# Sheet1.net
KiCad netlist of a schematic drawn in Altium Designer
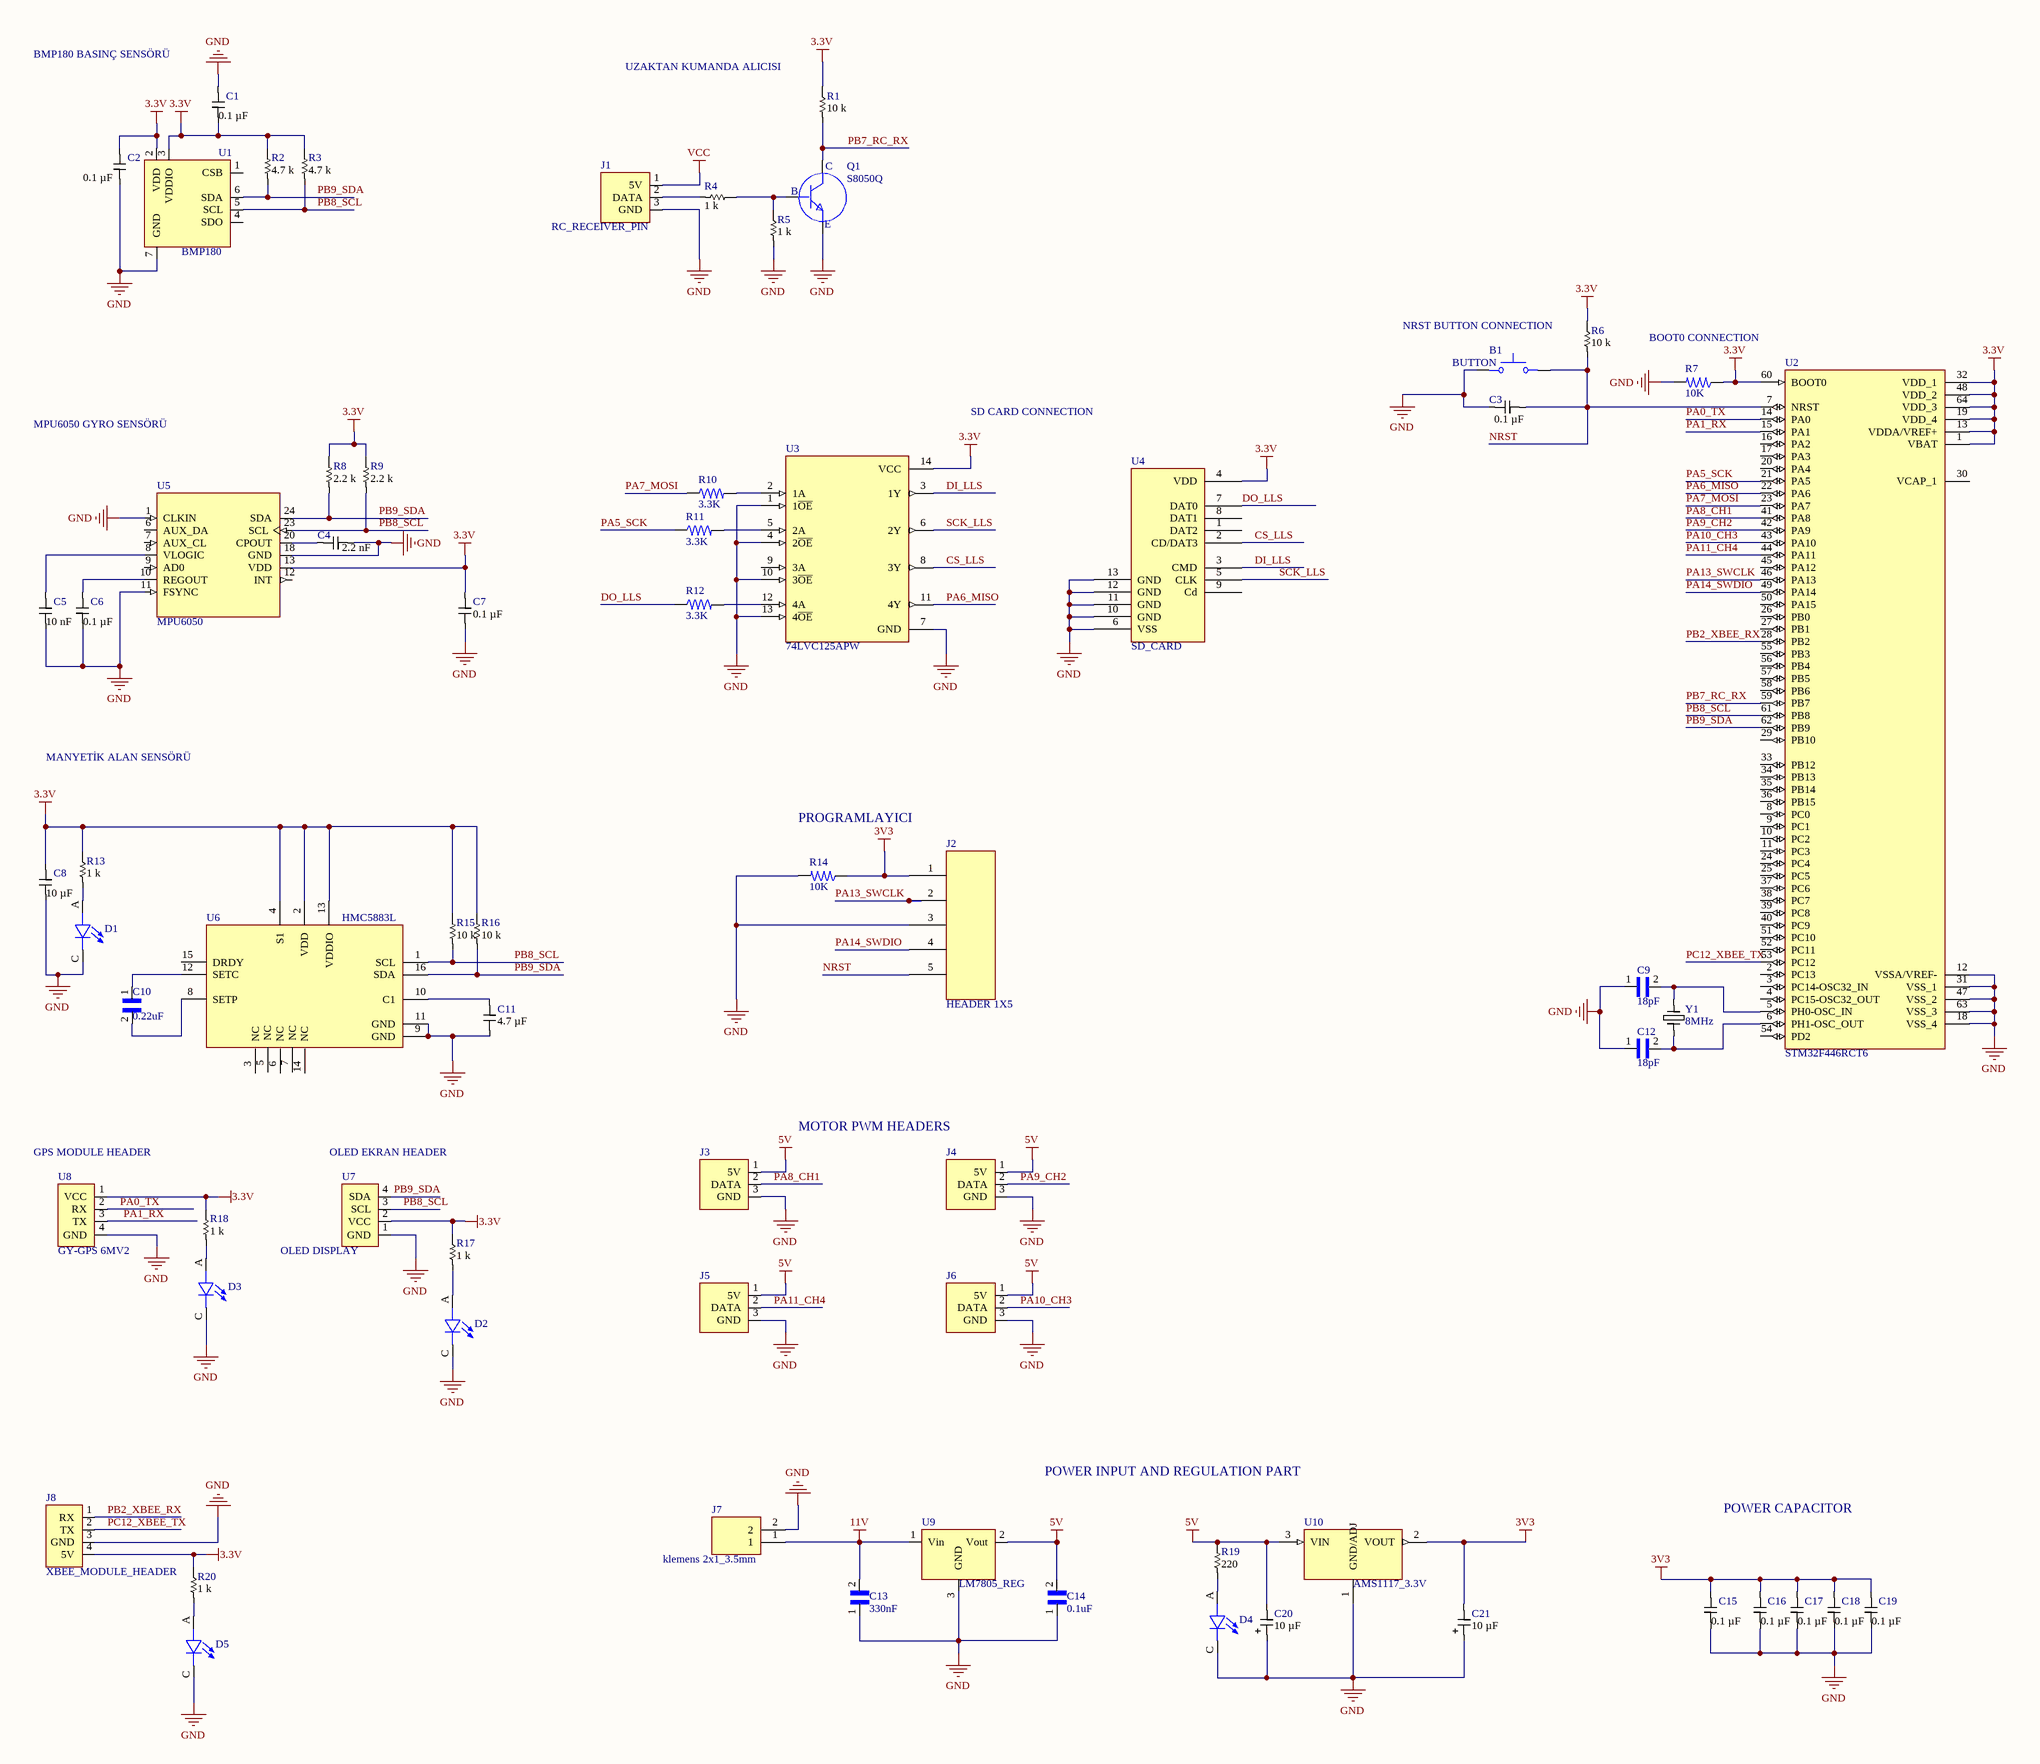
[diagram p0: Sheet1.SchDoc]

(export (version "E")
  (design (tool "Eeschema 10.0.6"))
  (components
    (comp (ref "B1") (value "BUTTON") (footprint "BUTTON") (libsource (lib "Schlib1") (part "BUTTON")))
    (comp (ref "C1")
      (value "CL10B104KB8NNNC")
      (footprint "SAMSUNG_CAP_0603_090")
      (description "CAP CER 0.1UF 50V X7R 0603")
      (fields (field (name "CAPACITANCE") "0.1 µF"))
      (libsource (lib "Ceramic Capacitors") (part "CL10B104KB8NNNC"))
    )
    (comp (ref "C2")
      (value "CL10B104KB8NNNC")
      (footprint "SAMSUNG_CAP_0603_090")
      (description "CAP CER 0.1UF 50V X7R 0603")
      (fields (field (name "CAPACITANCE") "0.1 µF"))
      (libsource (lib "Ceramic Capacitors") (part "CL10B104KB8NNNC"))
    )
    (comp (ref "C3")
      (value "CL10B104KB8NNNC")
      (footprint "SAMSUNG_CAP_0603_090")
      (description "CAP CER 0.1UF 50V X7R 0603")
      (fields (field (name "CAPACITANCE") "0.1 µF"))
      (libsource (lib "Ceramic Capacitors") (part "CL10B104KB8NNNC"))
    )
    (comp (ref "C4")
      (value "CL10B222KB8NNNC")
      (footprint "SAMSUNG_CAP_0603_090")
      (description "CAP CER 2200PF 50V X7R 0603")
      (fields (field (name "CAPACITANCE") "2.2 nF"))
      (libsource (lib "Ceramic Capacitors") (part "CL10B222KB8NNNC"))
    )
    (comp (ref "C5")
      (value "CL10B103KB8NNNL")
      (footprint "SAMSUNG_CAP_0603_090")
      (description "CAP CER 10000PF 50V X7R 0603")
      (fields (field (name "CAPACITANCE") "10 nF"))
      (libsource (lib "Ceramic Capacitors") (part "CL10B103KB8NNNL"))
    )
    (comp (ref "C6")
      (value "CL10B104KB8NNNC")
      (footprint "SAMSUNG_CAP_0603_090")
      (description "CAP CER 0.1UF 50V X7R 0603")
      (fields (field (name "CAPACITANCE") "0.1 µF"))
      (libsource (lib "Ceramic Capacitors") (part "CL10B104KB8NNNC"))
    )
    (comp (ref "C7")
      (value "CL10B104KB8NNNC")
      (footprint "SAMSUNG_CAP_0603_090")
      (description "CAP CER 0.1UF 50V X7R 0603")
      (fields (field (name "CAPACITANCE") "0.1 µF"))
      (libsource (lib "Ceramic Capacitors") (part "CL10B104KB8NNNC"))
    )
    (comp (ref "C8")
      (value "CL21B106KPQNNNE")
      (footprint "SAMSUNG_CAP_0805_140")
      (description "CAP CER 10UF 10V X7R 0805")
      (fields (field (name "CAPACITANCE") "10 µF"))
      (libsource (lib "Ceramic Capacitors") (part "CL21B106KPQNNNE"))
    )
    (comp (ref "C9")
      (value "18pF")
      (footprint "18pF capacitor")
      (libsource (lib "Schlib1") (part "capacitor 18pF"))
    )
    (comp (ref "C10")
      (value "0.22uF")
      (footprint "0.22uF CAPACITOR")
      (libsource (lib "Schlib1") (part "0.22uF CAPACITOR"))
    )
    (comp (ref "C11")
      (value "CL21A475KACLRNC")
      (footprint "SAMSUNG_CAP_0805_095")
      (description "CAP CER 4.7UF 25V X5R 0805")
      (fields (field (name "CAPACITANCE") "4.7 µF"))
      (libsource (lib "Ceramic Capacitors") (part "CL21A475KACLRNC"))
    )
    (comp (ref "C12")
      (value "18pF")
      (footprint "18pF capacitor")
      (libsource (lib "Schlib1") (part "capacitor 18pF"))
    )
    (comp (ref "C13")
      (value "330nF")
      (footprint "1206CAPACITOR")
      (libsource (lib "Sch1-schlib") (part "1206CAPACITOR"))
    )
    (comp (ref "C14")
      (value "0.1uF")
      (footprint "1206CAPACITOR")
      (libsource (lib "Sch1-schlib") (part "1206CAPACITOR"))
    )
    (comp (ref "C15")
      (value "CL10B104KB8NNNC")
      (footprint "SAMSUNG_CAP_0603_090")
      (description "CAP CER 0.1UF 50V X7R 0603")
      (fields (field (name "CAPACITANCE") "0.1 µF"))
      (libsource (lib "Ceramic Capacitors") (part "CL10B104KB8NNNC"))
    )
    (comp (ref "C16")
      (value "CL10B104KB8NNNC")
      (footprint "SAMSUNG_CAP_0603_090")
      (description "CAP CER 0.1UF 50V X7R 0603")
      (fields (field (name "CAPACITANCE") "0.1 µF"))
      (libsource (lib "Ceramic Capacitors") (part "CL10B104KB8NNNC"))
    )
    (comp (ref "C17")
      (value "CL10B104KB8NNNC")
      (footprint "SAMSUNG_CAP_0603_090")
      (description "CAP CER 0.1UF 50V X7R 0603")
      (fields (field (name "CAPACITANCE") "0.1 µF"))
      (libsource (lib "Ceramic Capacitors") (part "CL10B104KB8NNNC"))
    )
    (comp (ref "C18")
      (value "CL10B104KB8NNNC")
      (footprint "SAMSUNG_CAP_0603_090")
      (description "CAP CER 0.1UF 50V X7R 0603")
      (fields (field (name "CAPACITANCE") "0.1 µF"))
      (libsource (lib "Ceramic Capacitors") (part "CL10B104KB8NNNC"))
    )
    (comp (ref "C19")
      (value "CL10B104KB8NNNC")
      (footprint "SAMSUNG_CAP_0603_090")
      (description "CAP CER 0.1UF 50V X7R 0603")
      (fields (field (name "CAPACITANCE") "0.1 µF"))
      (libsource (lib "Ceramic Capacitors") (part "CL10B104KB8NNNC"))
    )
    (comp (ref "C20")
      (value "T491B106M016AT")
      (footprint "KEMET_CAP_TAN-B")
      (description "CAP TANT 10UF 20% 16V 1411")
      (fields (field (name "CAPACITANCE") "10 µF"))
      (libsource (lib "Tantalum Capacitors") (part "T491B106M016AT"))
    )
    (comp (ref "C21")
      (value "T491B106M016AT")
      (footprint "KEMET_CAP_TAN-B")
      (description "CAP TANT 10UF 20% 16V 1411")
      (fields (field (name "CAPACITANCE") "10 µF"))
      (libsource (lib "Tantalum Capacitors") (part "T491B106M016AT"))
    )
    (comp (ref "D1")
      (value "MP-2016-1100-30-80")
      (footprint "LED_MP-2016-1100-30-80")
      (description "LED Midpower Lighting series White, warm 3000K, 80 CRI, 27lm 3V 120mA 110Â°")
      (fields (field (name "MF") "Luminus Devices"))
      (libsource (lib "MP-2016-1100-30-80") (part "MP-2016-1100-30-80"))
    )
    (comp (ref "D2")
      (value "MP-2016-1100-30-80")
      (footprint "LED_MP-2016-1100-30-80")
      (description "LED Midpower Lighting series White, warm 3000K, 80 CRI, 27lm 3V 120mA 110Â°")
      (fields (field (name "MF") "Luminus Devices"))
      (libsource (lib "MP-2016-1100-30-80") (part "MP-2016-1100-30-80"))
    )
    (comp (ref "D3")
      (value "MP-2016-1100-30-80")
      (footprint "LED_MP-2016-1100-30-80")
      (description "LED Midpower Lighting series White, warm 3000K, 80 CRI, 27lm 3V 120mA 110Â°")
      (fields (field (name "MF") "Luminus Devices"))
      (libsource (lib "MP-2016-1100-30-80") (part "MP-2016-1100-30-80"))
    )
    (comp (ref "D4")
      (value "MP-2016-1100-30-80")
      (footprint "LED_MP-2016-1100-30-80")
      (description "LED Midpower Lighting series White, warm 3000K, 80 CRI, 27lm 3V 120mA 110Â°")
      (fields (field (name "MF") "Luminus Devices"))
      (libsource (lib "MP-2016-1100-30-80") (part "MP-2016-1100-30-80"))
    )
    (comp (ref "D5")
      (value "MP-2016-1100-30-80")
      (footprint "LED_MP-2016-1100-30-80")
      (description "LED Midpower Lighting series White, warm 3000K, 80 CRI, 27lm 3V 120mA 110Â°")
      (fields (field (name "MF") "Luminus Devices"))
      (libsource (lib "MP-2016-1100-30-80") (part "MP-2016-1100-30-80"))
    )
    (comp (ref "J1")
      (value "RC_RECEIVER_PIN")
      (footprint "RC_RECEIVER_PIN")
      (libsource (lib "Schlib1") (part "RC_RECEIVER_PIN"))
    )
    (comp (ref "J2")
      (value "HEADER 1X5")
      (footprint "HEADER 1X5_2.54mm")
      (libsource (lib "Sch1-schlib") (part "HEADER 1X5"))
    )
    (comp (ref "J3")
      (value "MOTOR_PWM_HEADER")
      (footprint "MOTOR_PWM_HEADER")
      (libsource (lib "Schlib1") (part "MOTOR_PWM_HEADER"))
    )
    (comp (ref "J4")
      (value "MOTOR_PWM_HEADER")
      (footprint "MOTOR_PWM_HEADER")
      (libsource (lib "Schlib1") (part "MOTOR_PWM_HEADER"))
    )
    (comp (ref "J5")
      (value "MOTOR_PWM_HEADER")
      (footprint "MOTOR_PWM_HEADER")
      (libsource (lib "Schlib1") (part "MOTOR_PWM_HEADER"))
    )
    (comp (ref "J6")
      (value "MOTOR_PWM_HEADER")
      (footprint "MOTOR_PWM_HEADER")
      (libsource (lib "Schlib1") (part "MOTOR_PWM_HEADER"))
    )
    (comp (ref "J7")
      (value "klemens 2x1_3.5mm")
      (footprint "KLEMENS 2X1_3.5mm - duplicate")
      (libsource (lib "Sch1-schlib") (part "klemens 2x1_3.5mm"))
    )
    (comp (ref "J8")
      (value "XBEE_MODULE_HEADER")
      (footprint "XBEE_MODULE_HEADER")
      (libsource (lib "Schlib1") (part "XBEE_MODULE_HEADER"))
    )
    (comp (ref "Q1")
      (value "S8050Q")
      (footprint "S8050Q")
      (description "BJT TRANSİSTOR 25V 0.5mA")
      (libsource (lib "Schlib1") (part "S8050Q"))
    )
    (comp (ref "R1")
      (value "0603SAJ0103T5E")
      (footprint "ROYALOHM_RES_0603")
      (description "RES SMD 10K OHM 5% 1/10W 0603")
      (fields (field (name "RESISTANCE") "10 k"))
      (libsource (lib "Chip Resistor - Surface Mount") (part "0603SAJ0103T5E"))
    )
    (comp (ref "R2")
      (value "0603SAJ0472TDE")
      (footprint "ROYALOHM_RES_0603")
      (description "RES SMD 4.7K OHM 5% 1/10W 0603")
      (fields (field (name "RESISTANCE") "4.7 k"))
      (libsource (lib "Chip Resistor - Surface Mount") (part "0603SAJ0472TDE"))
    )
    (comp (ref "R3")
      (value "0603SAJ0472TDE")
      (footprint "ROYALOHM_RES_0603")
      (description "RES SMD 4.7K OHM 5% 1/10W 0603")
      (fields (field (name "RESISTANCE") "4.7 k"))
      (libsource (lib "Chip Resistor - Surface Mount") (part "0603SAJ0472TDE"))
    )
    (comp (ref "R4")
      (value "0603SAJ0102T5E")
      (footprint "ROYALOHM_RES_0603")
      (description "RES SMD 1K OHM 5% 1/10W 0603")
      (fields (field (name "RESISTANCE") "1 k"))
      (libsource (lib "Chip Resistor - Surface Mount") (part "0603SAJ0102T5E"))
    )
    (comp (ref "R5")
      (value "0603SAJ0102T5E")
      (footprint "ROYALOHM_RES_0603")
      (description "RES SMD 1K OHM 5% 1/10W 0603")
      (fields (field (name "RESISTANCE") "1 k"))
      (libsource (lib "Chip Resistor - Surface Mount") (part "0603SAJ0102T5E"))
    )
    (comp (ref "R6")
      (value "0603SAJ0103T5E")
      (footprint "ROYALOHM_RES_0603")
      (description "RES SMD 10K OHM 5% 1/10W 0603")
      (fields (field (name "RESISTANCE") "10 k"))
      (libsource (lib "Chip Resistor - Surface Mount") (part "0603SAJ0103T5E"))
    )
    (comp (ref "R7") (value "10K") (footprint "RES") (libsource (lib "Sch1-schlib") (part "RES")))
    (comp (ref "R8")
      (value "0805S8J0222T5E")
      (footprint "ROYALOHM_RES_0805")
      (description "RES SMD 2.2K OHM 5% 1/8W 0805")
      (fields (field (name "RESISTANCE") "2.2 k"))
      (libsource (lib "Chip Resistor - Surface Mount") (part "0805S8J0222T5E"))
    )
    (comp (ref "R9")
      (value "0805S8J0222T5E")
      (footprint "ROYALOHM_RES_0805")
      (description "RES SMD 2.2K OHM 5% 1/8W 0805")
      (fields (field (name "RESISTANCE") "2.2 k"))
      (libsource (lib "Chip Resistor - Surface Mount") (part "0805S8J0222T5E"))
    )
    (comp (ref "R10")
      (value "3.3K")
      (footprint "0805 cap RES")
      (description "RES 0.33 OHM 1% 1/4W 0805              0805 cap RES")
      (libsource (lib "Schlib1") (part "0805 cap RES"))
    )
    (comp (ref "R11")
      (value "3.3K")
      (footprint "0805 cap RES")
      (description "RES 0.33 OHM 1% 1/4W 0805              0805 cap RES")
      (libsource (lib "Schlib1") (part "0805 cap RES"))
    )
    (comp (ref "R12")
      (value "3.3K")
      (footprint "0805 cap RES")
      (description "RES 0.33 OHM 1% 1/4W 0805              0805 cap RES")
      (libsource (lib "Schlib1") (part "0805 cap RES"))
    )
    (comp (ref "R13")
      (value "0603SAJ0102T5E")
      (footprint "ROYALOHM_RES_0603")
      (description "RES SMD 1K OHM 5% 1/10W 0603")
      (fields (field (name "RESISTANCE") "1 k"))
      (libsource (lib "Chip Resistor - Surface Mount") (part "0603SAJ0102T5E"))
    )
    (comp (ref "R14") (value "10K") (footprint "RES") (libsource (lib "Sch1-schlib") (part "RES")))
    (comp (ref "R15")
      (value "0603SAJ0103T5E")
      (footprint "ROYALOHM_RES_0603")
      (description "RES SMD 10K OHM 5% 1/10W 0603")
      (fields (field (name "RESISTANCE") "10 k"))
      (libsource (lib "Chip Resistor - Surface Mount") (part "0603SAJ0103T5E"))
    )
    (comp (ref "R16")
      (value "0603SAJ0103T5E")
      (footprint "ROYALOHM_RES_0603")
      (description "RES SMD 10K OHM 5% 1/10W 0603")
      (fields (field (name "RESISTANCE") "10 k"))
      (libsource (lib "Chip Resistor - Surface Mount") (part "0603SAJ0103T5E"))
    )
    (comp (ref "R17")
      (value "0603SAJ0102T5E")
      (footprint "ROYALOHM_RES_0603")
      (description "RES SMD 1K OHM 5% 1/10W 0603")
      (fields (field (name "RESISTANCE") "1 k"))
      (libsource (lib "Chip Resistor - Surface Mount") (part "0603SAJ0102T5E"))
    )
    (comp (ref "R18")
      (value "0603SAJ0102T5E")
      (footprint "ROYALOHM_RES_0603")
      (description "RES SMD 1K OHM 5% 1/10W 0603")
      (fields (field (name "RESISTANCE") "1 k"))
      (libsource (lib "Chip Resistor - Surface Mount") (part "0603SAJ0102T5E"))
    )
    (comp (ref "R19")
      (value "0603SAJ0221T5E")
      (footprint "ROYALOHM_RES_0603")
      (description "RES SMD 220R OHM 5% 1/10W 0603")
      (fields (field (name "RESISTANCE") "220"))
      (libsource (lib "Chip Resistor - Surface Mount") (part "0603SAJ0221T5E"))
    )
    (comp (ref "R20")
      (value "0603SAJ0102T5E")
      (footprint "ROYALOHM_RES_0603")
      (description "RES SMD 1K OHM 5% 1/10W 0603")
      (fields (field (name "RESISTANCE") "1 k"))
      (libsource (lib "Chip Resistor - Surface Mount") (part "0603SAJ0102T5E"))
    )
    (comp (ref "U1")
      (value "BMP180")
      (footprint "BMP180")
      (description "PRESSURE SENSOR")
      (libsource (lib "Schlib1") (part "BMP180"))
    )
    (comp (ref "U2")
      (value "STM32F446RCT6")
      (footprint "STM32F446RCT6")
      (libsource (lib "Schlib1") (part "STM32F446RCT6"))
    )
    (comp (ref "U3")
      (value "74LVC125APW")
      (footprint "74LVC125APW")
      (libsource (lib "Schlib1") (part "74LVC125APW"))
    )
    (comp (ref "U4") (value "SD_CARD") (footprint "SD_CARD") (libsource (lib "Schlib1") (part "SD_CARD")))
    (comp (ref "U5") (value "MPU6050") (footprint "MPU6050") (libsource (lib "Schlib1") (part "MPU6050")))
    (comp (ref "U6") (value "HMC5883L") (footprint "HMC5883L") (libsource (lib "Schlib1") (part "HMC5883L")))
    (comp (ref "U7")
      (value "OLED DISPLAY")
      (footprint "OLED DISPLAY")
      (libsource (lib "Schlib1") (part "OLED DISPLAY"))
    )
    (comp (ref "U8")
      (value "GY-GPS 6MV2")
      (footprint "GY-GPS 6MV2")
      (libsource (lib "Schlib1") (part "GY-GPS 6MV2"))
    )
    (comp (ref "U9")
      (value "LM7805_REG")
      (footprint "DPAK228P968X230-3N")
      (libsource (lib "Schlib1") (part "LM7805_REG"))
    )
    (comp (ref "U10")
      (value "AMS1117_3.3V")
      (footprint "AMS1117_3.3V")
      (libsource (lib "Schlib1") (part "AMS1117_3.3V"))
    )
    (comp (ref "Y1")
      (value "8MHz")
      (footprint "ABM3-8.000MHZ-D2Y-T")
      (libsource (lib "Schlib1") (part "ABM3-8.000MHZ-D2Y-T"))
    )
  )
  (nets
    (net (code "1") (name "/CS_LLS") (class "Default")
      (node (ref "U3") (pin "8") (pinfunction "3Y_8") (pintype "output"))
      (node (ref "U4") (pin "2") (pinfunction "CD/DAT3_2") (pintype "passive"))
    )
    (net (code "2") (name "/DI_LLS") (class "Default")
      (node (ref "U3") (pin "3") (pinfunction "1Y_3") (pintype "output"))
      (node (ref "U4") (pin "3") (pinfunction "CMD_3") (pintype "passive"))
    )
    (net (code "3") (name "/DO_LLS") (class "Default")
      (node (ref "R12") (pin "1") (pinfunction "1_1") (pintype "passive"))
      (node (ref "U4") (pin "7") (pinfunction "DAT0_7") (pintype "passive"))
    )
    (net (code "4") (name "/NRST") (class "Default")
      (node (ref "B1") (pin "3") (pinfunction "3_3") (pintype "passive"))
      (node (ref "C3") (pin "2") (pinfunction "2_2") (pintype "passive"))
      (node (ref "J2") (pin "5") (pintype "passive"))
      (node (ref "R6") (pin "1") (pinfunction "1_1") (pintype "passive"))
      (node (ref "U2") (pin "7") (pinfunction "NRST_7") (pintype "bidirectional"))
    )
    (net (code "5") (name "/PA0_TX") (class "Default")
      (node (ref "U2") (pin "14") (pinfunction "PA0_14") (pintype "bidirectional"))
      (node (ref "U8") (pin "2") (pinfunction "RX_2") (pintype "passive"))
    )
    (net (code "6") (name "/PA1_RX") (class "Default")
      (node (ref "U2") (pin "15") (pinfunction "PA1_15") (pintype "bidirectional"))
      (node (ref "U8") (pin "3") (pinfunction "TX_3") (pintype "passive"))
    )
    (net (code "7") (name "/PA5_SCK") (class "Default")
      (node (ref "R11") (pin "1") (pinfunction "1_1") (pintype "passive"))
      (node (ref "U2") (pin "21") (pinfunction "PA5_21") (pintype "bidirectional"))
    )
    (net (code "8") (name "/PA6_MISO") (class "Default")
      (node (ref "U2") (pin "22") (pinfunction "PA6_22") (pintype "bidirectional"))
      (node (ref "U3") (pin "11") (pinfunction "4Y_11") (pintype "output"))
    )
    (net (code "9") (name "/PA7_MOSI") (class "Default")
      (node (ref "R10") (pin "1") (pinfunction "1_1") (pintype "passive"))
      (node (ref "U2") (pin "23") (pinfunction "PA7_23") (pintype "bidirectional"))
    )
    (net (code "10") (name "/PA8_CH1") (class "Default")
      (node (ref "J3") (pin "2") (pinfunction "DATA_2") (pintype "passive"))
      (node (ref "U2") (pin "41") (pinfunction "PA8_41") (pintype "bidirectional"))
    )
    (net (code "11") (name "/PA9_CH2") (class "Default")
      (node (ref "J4") (pin "2") (pinfunction "DATA_2") (pintype "passive"))
      (node (ref "U2") (pin "42") (pinfunction "PA9_42") (pintype "bidirectional"))
    )
    (net (code "12") (name "/PA10_CH3") (class "Default")
      (node (ref "J6") (pin "2") (pinfunction "DATA_2") (pintype "passive"))
      (node (ref "U2") (pin "43") (pinfunction "PA10_43") (pintype "bidirectional"))
    )
    (net (code "13") (name "/PA11_CH4") (class "Default")
      (node (ref "J5") (pin "2") (pinfunction "DATA_2") (pintype "passive"))
      (node (ref "U2") (pin "44") (pinfunction "PA11_44") (pintype "bidirectional"))
    )
    (net (code "14") (name "/PA13_SWCLK") (class "Default")
      (node (ref "J2") (pin "2") (pintype "passive"))
      (node (ref "U2") (pin "46") (pinfunction "PA13_46") (pintype "bidirectional"))
    )
    (net (code "15") (name "/PA14_SWDIO") (class "Default")
      (node (ref "J2") (pin "4") (pintype "passive"))
      (node (ref "U2") (pin "49") (pinfunction "PA14_49") (pintype "bidirectional"))
    )
    (net (code "16") (name "/PB2_XBEE_RX") (class "Default")
      (node (ref "J8") (pin "1") (pinfunction "RX_1") (pintype "passive"))
      (node (ref "U2") (pin "28") (pinfunction "PB2_28") (pintype "bidirectional"))
    )
    (net (code "17") (name "/PB7_RC_RX") (class "Default")
      (node (ref "Q1") (pin "3") (pinfunction "C_3") (pintype "passive"))
      (node (ref "R1") (pin "1") (pinfunction "1_1") (pintype "passive"))
      (node (ref "U2") (pin "59") (pinfunction "PB7_59") (pintype "bidirectional"))
    )
    (net (code "18") (name "/PB8_SCL") (class "Default")
      (node (ref "R15") (pin "1") (pinfunction "1_1") (pintype "passive"))
      (node (ref "R3") (pin "1") (pinfunction "1_1") (pintype "passive"))
      (node (ref "R9") (pin "1") (pinfunction "1_1") (pintype "passive"))
      (node (ref "U1") (pin "5") (pinfunction "SCL_5") (pintype "passive"))
      (node (ref "U2") (pin "61") (pinfunction "PB8_61") (pintype "bidirectional"))
      (node (ref "U5") (pin "23") (pinfunction "SCL_23") (pintype "input"))
      (node (ref "U6") (pin "1") (pinfunction "SCL_1") (pintype "passive"))
      (node (ref "U7") (pin "3") (pinfunction "SCL_3") (pintype "passive"))
    )
    (net (code "19") (name "/PB9_SDA") (class "Default")
      (node (ref "R16") (pin "1") (pinfunction "1_1") (pintype "passive"))
      (node (ref "R2") (pin "1") (pinfunction "1_1") (pintype "passive"))
      (node (ref "R8") (pin "1") (pinfunction "1_1") (pintype "passive"))
      (node (ref "U1") (pin "6") (pinfunction "SDA_6") (pintype "passive"))
      (node (ref "U2") (pin "62") (pinfunction "PB9_62") (pintype "bidirectional"))
      (node (ref "U5") (pin "24") (pinfunction "SDA_24") (pintype "bidirectional"))
      (node (ref "U6") (pin "16") (pinfunction "SDA_16") (pintype "passive"))
      (node (ref "U7") (pin "4") (pinfunction "SDA_4") (pintype "passive"))
    )
    (net (code "20") (name "/PC12_XBEE_TX") (class "Default")
      (node (ref "J8") (pin "2") (pinfunction "TX_2") (pintype "passive"))
      (node (ref "U2") (pin "53") (pinfunction "PC12_53") (pintype "bidirectional"))
    )
    (net (code "21") (name "/SCK_LLS") (class "Default")
      (node (ref "U3") (pin "6") (pinfunction "2Y_6") (pintype "output"))
      (node (ref "U4") (pin "5") (pinfunction "CLK_5") (pintype "passive"))
    )
    (net (code "22") (name "3.3V") (class "Default")
      (node (ref "C1") (pin "2") (pinfunction "2_2") (pintype "passive"))
      (node (ref "C2") (pin "1") (pinfunction "1_1") (pintype "passive"))
      (node (ref "C7") (pin "2") (pinfunction "2_2") (pintype "passive"))
      (node (ref "C8") (pin "2") (pinfunction "2_2") (pintype "passive"))
      (node (ref "J8") (pin "4") (pinfunction "5V_4") (pintype "passive"))
      (node (ref "R1") (pin "2") (pinfunction "2_2") (pintype "passive"))
      (node (ref "R13") (pin "2") (pinfunction "2_2") (pintype "passive"))
      (node (ref "R15") (pin "2") (pinfunction "2_2") (pintype "passive"))
      (node (ref "R16") (pin "2") (pinfunction "2_2") (pintype "passive"))
      (node (ref "R17") (pin "2") (pinfunction "2_2") (pintype "passive"))
      (node (ref "R18") (pin "2") (pinfunction "2_2") (pintype "passive"))
      (node (ref "R2") (pin "2") (pinfunction "2_2") (pintype "passive"))
      (node (ref "R20") (pin "2") (pinfunction "2_2") (pintype "passive"))
      (node (ref "R3") (pin "2") (pinfunction "2_2") (pintype "passive"))
      (node (ref "R6") (pin "2") (pinfunction "2_2") (pintype "passive"))
      (node (ref "R7") (pin "1") (pinfunction "1_1") (pintype "passive"))
      (node (ref "R8") (pin "2") (pinfunction "2_2") (pintype "passive"))
      (node (ref "R9") (pin "2") (pinfunction "2_2") (pintype "passive"))
      (node (ref "U1") (pin "2") (pinfunction "VDD_2") (pintype "passive"))
      (node (ref "U1") (pin "3") (pinfunction "VDDIO_3") (pintype "passive"))
      (node (ref "U2") (pin "1") (pinfunction "VBAT_1") (pintype "power_in"))
      (node (ref "U2") (pin "13") (pinfunction "VDDA/VREF+_13") (pintype "power_in"))
      (node (ref "U2") (pin "19") (pinfunction "VDD_4_19") (pintype "power_in"))
      (node (ref "U2") (pin "32") (pinfunction "VDD_1_32") (pintype "power_in"))
      (node (ref "U2") (pin "48") (pinfunction "VDD_2_48") (pintype "power_in"))
      (node (ref "U2") (pin "60") (pinfunction "BOOT0_60") (pintype "input"))
      (node (ref "U2") (pin "64") (pinfunction "VDD_3_64") (pintype "power_in"))
      (node (ref "U3") (pin "14") (pinfunction "VCC_14") (pintype "power_in"))
      (node (ref "U4") (pin "4") (pinfunction "VDD_4") (pintype "passive"))
      (node (ref "U5") (pin "13") (pinfunction "VDD_13") (pintype "power_in"))
      (node (ref "U6") (pin "13") (pinfunction "VDDIO_13") (pintype "passive"))
      (node (ref "U6") (pin "2") (pinfunction "VDD_2") (pintype "passive"))
      (node (ref "U6") (pin "4") (pinfunction "S1_4") (pintype "passive"))
      (node (ref "U7") (pin "2") (pinfunction "VCC_2") (pintype "passive"))
      (node (ref "U8") (pin "1") (pinfunction "VCC_1") (pintype "passive"))
    )
    (net (code "23") (name "3V3") (class "Default")
      (node (ref "C15") (pin "1") (pinfunction "1_1") (pintype "passive"))
      (node (ref "C16") (pin "1") (pinfunction "1_1") (pintype "passive"))
      (node (ref "C17") (pin "1") (pinfunction "1_1") (pintype "passive"))
      (node (ref "C18") (pin "1") (pinfunction "1_1") (pintype "passive"))
      (node (ref "C19") (pin "1") (pinfunction "1_1") (pintype "passive"))
      (node (ref "C21") (pin "2") (pinfunction "2_2") (pintype "passive"))
      (node (ref "J2") (pin "1") (pintype "passive"))
      (node (ref "R14") (pin "1") (pinfunction "1_1") (pintype "passive"))
      (node (ref "U10") (pin "2") (pinfunction "VOUT_2") (pintype "output"))
    )
    (net (code "24") (name "5V") (class "Default")
      (node (ref "C14") (pin "2") (pinfunction "2_2") (pintype "passive"))
      (node (ref "C20") (pin "2") (pinfunction "2_2") (pintype "passive"))
      (node (ref "J3") (pin "1") (pinfunction "5V_1") (pintype "passive"))
      (node (ref "J4") (pin "1") (pinfunction "5V_1") (pintype "passive"))
      (node (ref "J5") (pin "1") (pinfunction "5V_1") (pintype "passive"))
      (node (ref "J6") (pin "1") (pinfunction "5V_1") (pintype "passive"))
      (node (ref "R19") (pin "2") (pinfunction "2_2") (pintype "passive"))
      (node (ref "U10") (pin "3") (pinfunction "VIN_3") (pintype "input"))
      (node (ref "U9") (pin "2") (pinfunction "Vout_2") (pintype "passive"))
    )
    (net (code "25") (name "11V") (class "Default")
      (node (ref "C13") (pin "2") (pinfunction "2_2") (pintype "passive"))
      (node (ref "J7") (pin "1") (pinfunction "1_1") (pintype "passive"))
      (node (ref "U9") (pin "1") (pinfunction "Vin_1") (pintype "passive"))
    )
    (net (code "26") (name "GND") (class "Default")
      (node (ref "B1") (pin "1") (pinfunction "1_1") (pintype "passive"))
      (node (ref "C1") (pin "1") (pinfunction "1_1") (pintype "passive"))
      (node (ref "C11") (pin "1") (pinfunction "1_1") (pintype "passive"))
      (node (ref "C12") (pin "1") (pinfunction "1_1") (pintype "passive"))
      (node (ref "C13") (pin "1") (pinfunction "1_1") (pintype "passive"))
      (node (ref "C14") (pin "1") (pinfunction "1_1") (pintype "passive"))
      (node (ref "C15") (pin "2") (pinfunction "2_2") (pintype "passive"))
      (node (ref "C16") (pin "2") (pinfunction "2_2") (pintype "passive"))
      (node (ref "C17") (pin "2") (pinfunction "2_2") (pintype "passive"))
      (node (ref "C18") (pin "2") (pinfunction "2_2") (pintype "passive"))
      (node (ref "C19") (pin "2") (pinfunction "2_2") (pintype "passive"))
      (node (ref "C2") (pin "2") (pinfunction "2_2") (pintype "passive"))
      (node (ref "C20") (pin "1") (pinfunction "1_1") (pintype "passive"))
      (node (ref "C21") (pin "1") (pinfunction "1_1") (pintype "passive"))
      (node (ref "C3") (pin "1") (pinfunction "1_1") (pintype "passive"))
      (node (ref "C4") (pin "2") (pinfunction "2_2") (pintype "passive"))
      (node (ref "C5") (pin "1") (pinfunction "1_1") (pintype "passive"))
      (node (ref "C6") (pin "2") (pinfunction "2_2") (pintype "passive"))
      (node (ref "C7") (pin "1") (pinfunction "1_1") (pintype "passive"))
      (node (ref "C8") (pin "1") (pinfunction "1_1") (pintype "passive"))
      (node (ref "C9") (pin "1") (pinfunction "1_1") (pintype "passive"))
      (node (ref "D1") (pin "C") (pinfunction "C_C") (pintype "passive"))
      (node (ref "D2") (pin "C") (pinfunction "C_C") (pintype "passive"))
      (node (ref "D3") (pin "C") (pinfunction "C_C") (pintype "passive"))
      (node (ref "D4") (pin "C") (pinfunction "C_C") (pintype "passive"))
      (node (ref "D5") (pin "C") (pinfunction "C_C") (pintype "passive"))
      (node (ref "J1") (pin "3") (pinfunction "GND_3") (pintype "passive"))
      (node (ref "J2") (pin "3") (pintype "passive"))
      (node (ref "J3") (pin "3") (pinfunction "GND_3") (pintype "passive"))
      (node (ref "J4") (pin "3") (pinfunction "GND_3") (pintype "passive"))
      (node (ref "J5") (pin "3") (pinfunction "GND_3") (pintype "passive"))
      (node (ref "J6") (pin "3") (pinfunction "GND_3") (pintype "passive"))
      (node (ref "J7") (pin "2") (pinfunction "2_2") (pintype "passive"))
      (node (ref "J8") (pin "3") (pinfunction "GND_3") (pintype "passive"))
      (node (ref "Q1") (pin "2") (pinfunction "E_2") (pintype "passive"))
      (node (ref "R14") (pin "2") (pinfunction "2_2") (pintype "passive"))
      (node (ref "R5") (pin "1") (pinfunction "1_1") (pintype "passive"))
      (node (ref "R7") (pin "2") (pinfunction "2_2") (pintype "passive"))
      (node (ref "U1") (pin "7") (pinfunction "GND_7") (pintype "passive"))
      (node (ref "U10") (pin "1") (pinfunction "GND/ADJ_1") (pintype "power_in"))
      (node (ref "U2") (pin "12") (pinfunction "VSSA/VREF-_12") (pintype "power_in"))
      (node (ref "U2") (pin "18") (pinfunction "VSS_4_18") (pintype "power_in"))
      (node (ref "U2") (pin "31") (pinfunction "VSS_1_31") (pintype "power_in"))
      (node (ref "U2") (pin "47") (pinfunction "VSS_2_47") (pintype "power_in"))
      (node (ref "U2") (pin "63") (pinfunction "VSS_3_63") (pintype "power_in"))
      (node (ref "U3") (pin "1") (pinfunction "1~{OE}_1") (pintype "input"))
      (node (ref "U3") (pin "10") (pinfunction "3~{OE}_10") (pintype "input"))
      (node (ref "U3") (pin "13") (pinfunction "4~{OE}_13") (pintype "input"))
      (node (ref "U3") (pin "4") (pinfunction "2~{OE}_4") (pintype "input"))
      (node (ref "U3") (pin "7") (pinfunction "GND_7") (pintype "power_in"))
      (node (ref "U4") (pin "10") (pinfunction "GND_10") (pintype "passive"))
      (node (ref "U4") (pin "11") (pinfunction "GND_11") (pintype "passive"))
      (node (ref "U4") (pin "12") (pinfunction "GND_12") (pintype "passive"))
      (node (ref "U4") (pin "13") (pinfunction "GND_13") (pintype "passive"))
      (node (ref "U4") (pin "6") (pinfunction "VSS_6") (pintype "passive"))
      (node (ref "U5") (pin "1") (pinfunction "CLKIN_1") (pintype "input"))
      (node (ref "U5") (pin "11") (pinfunction "FSYNC_11") (pintype "input"))
      (node (ref "U5") (pin "18") (pinfunction "GND_18") (pintype "power_in"))
      (node (ref "U6") (pin "11") (pinfunction "GND_11") (pintype "passive"))
      (node (ref "U6") (pin "9") (pinfunction "GND_9") (pintype "passive"))
      (node (ref "U7") (pin "1") (pinfunction "GND_1") (pintype "passive"))
      (node (ref "U8") (pin "4") (pinfunction "GND_4") (pintype "passive"))
      (node (ref "U9") (pin "3") (pinfunction "GND_3") (pintype "passive"))
    )
    (net (code "27") (name "Net-(D1-PadA)") (class "Default")
      (node (ref "D1") (pin "A") (pinfunction "A_A") (pintype "passive"))
      (node (ref "R13") (pin "1") (pinfunction "1_1") (pintype "passive"))
    )
    (net (code "28") (name "Net-(D2-PadA)") (class "Default")
      (node (ref "D2") (pin "A") (pinfunction "A_A") (pintype "passive"))
      (node (ref "R17") (pin "1") (pinfunction "1_1") (pintype "passive"))
    )
    (net (code "29") (name "Net-(D3-PadA)") (class "Default")
      (node (ref "D3") (pin "A") (pinfunction "A_A") (pintype "passive"))
      (node (ref "R18") (pin "1") (pinfunction "1_1") (pintype "passive"))
    )
    (net (code "30") (name "Net-(D4-PadA)") (class "Default")
      (node (ref "D4") (pin "A") (pinfunction "A_A") (pintype "passive"))
      (node (ref "R19") (pin "1") (pinfunction "1_1") (pintype "passive"))
    )
    (net (code "31") (name "Net-(D5-PadA)") (class "Default")
      (node (ref "D5") (pin "A") (pinfunction "A_A") (pintype "passive"))
      (node (ref "R20") (pin "1") (pinfunction "1_1") (pintype "passive"))
    )
    (net (code "32") (name "Net-(J1-DATA)") (class "Default")
      (node (ref "J1") (pin "2") (pinfunction "DATA_2") (pintype "passive"))
      (node (ref "R4") (pin "1") (pinfunction "1_1") (pintype "passive"))
    )
    (net (code "33") (name "Net-(Q1-B)") (class "Default")
      (node (ref "Q1") (pin "1") (pinfunction "B_1") (pintype "passive"))
      (node (ref "R4") (pin "2") (pinfunction "2_2") (pintype "passive"))
      (node (ref "R5") (pin "2") (pinfunction "2_2") (pintype "passive"))
    )
    (net (code "34") (name "Net-(U2-PH0-OSC_IN)") (class "Default")
      (node (ref "C9") (pin "2") (pinfunction "2_2") (pintype "passive"))
      (node (ref "U2") (pin "5") (pinfunction "PH0-OSC_IN_5") (pintype "bidirectional"))
      (node (ref "Y1") (pin "2") (pinfunction "2_2") (pintype "passive"))
    )
    (net (code "35") (name "Net-(U2-PH1-OSC_OUT)") (class "Default")
      (node (ref "C12") (pin "2") (pinfunction "2_2") (pintype "passive"))
      (node (ref "U2") (pin "6") (pinfunction "PH1-OSC_OUT_6") (pintype "bidirectional"))
      (node (ref "Y1") (pin "1") (pinfunction "1_1") (pintype "passive"))
    )
    (net (code "36") (name "Net-(U3-1A)") (class "Default")
      (node (ref "R10") (pin "2") (pinfunction "2_2") (pintype "passive"))
      (node (ref "U3") (pin "2") (pinfunction "1A_2") (pintype "input"))
    )
    (net (code "37") (name "Net-(U3-2A)") (class "Default")
      (node (ref "R11") (pin "2") (pinfunction "2_2") (pintype "passive"))
      (node (ref "U3") (pin "5") (pinfunction "2A_5") (pintype "input"))
    )
    (net (code "38") (name "Net-(U3-4A)") (class "Default")
      (node (ref "R12") (pin "2") (pinfunction "2_2") (pintype "passive"))
      (node (ref "U3") (pin "12") (pinfunction "4A_12") (pintype "input"))
    )
    (net (code "39") (name "Net-(U5-CPOUT)") (class "Default")
      (node (ref "C4") (pin "1") (pinfunction "1_1") (pintype "passive"))
      (node (ref "U5") (pin "20") (pinfunction "CPOUT_20") (pintype "passive"))
    )
    (net (code "40") (name "Net-(U5-REGOUT)") (class "Default")
      (node (ref "C6") (pin "1") (pinfunction "1_1") (pintype "passive"))
      (node (ref "U5") (pin "10") (pinfunction "REGOUT_10") (pintype "passive"))
    )
    (net (code "41") (name "Net-(U5-VLOGIC)") (class "Default")
      (node (ref "C5") (pin "2") (pinfunction "2_2") (pintype "passive"))
      (node (ref "U5") (pin "8") (pinfunction "VLOGIC_8") (pintype "power_in"))
    )
    (net (code "42") (name "Net-(U6-C1)") (class "Default")
      (node (ref "C11") (pin "2") (pinfunction "2_2") (pintype "passive"))
      (node (ref "U6") (pin "10") (pinfunction "C1_10") (pintype "passive"))
    )
    (net (code "43") (name "Net-(U6-SETC)") (class "Default")
      (node (ref "C10") (pin "1") (pinfunction "1_1") (pintype "passive"))
      (node (ref "U6") (pin "12") (pinfunction "SETC_12") (pintype "passive"))
    )
    (net (code "44") (name "Net-(U6-SETP)") (class "Default")
      (node (ref "C10") (pin "2") (pinfunction "2_2") (pintype "passive"))
      (node (ref "U6") (pin "8") (pinfunction "SETP_8") (pintype "passive"))
    )
    (net (code "45") (name "VCC") (class "Default")
      (node (ref "J1") (pin "1") (pinfunction "5V_1") (pintype "passive"))
    )
    (net (code "46") (name "unconnected-(U1-CSB-Pad1)") (class "Default")
      (node (ref "U1") (pin "1") (pinfunction "CSB_1") (pintype "passive"))
    )
    (net (code "47") (name "unconnected-(U1-SDO-Pad4)") (class "Default")
      (node (ref "U1") (pin "4") (pinfunction "SDO_4") (pintype "passive"))
    )
    (net (code "48") (name "unconnected-(U2-PA2-Pad16)") (class "Default")
      (node (ref "U2") (pin "16") (pinfunction "PA2_16") (pintype "bidirectional"))
    )
    (net (code "49") (name "unconnected-(U2-PA3-Pad17)") (class "Default")
      (node (ref "U2") (pin "17") (pinfunction "PA3_17") (pintype "bidirectional"))
    )
    (net (code "50") (name "unconnected-(U2-PA4-Pad20)") (class "Default")
      (node (ref "U2") (pin "20") (pinfunction "PA4_20") (pintype "bidirectional"))
    )
    (net (code "51") (name "unconnected-(U2-PA12-Pad45)") (class "Default")
      (node (ref "U2") (pin "45") (pinfunction "PA12_45") (pintype "bidirectional"))
    )
    (net (code "52") (name "unconnected-(U2-PA15-Pad50)") (class "Default")
      (node (ref "U2") (pin "50") (pinfunction "PA15_50") (pintype "bidirectional"))
    )
    (net (code "53") (name "unconnected-(U2-PB0-Pad26)") (class "Default")
      (node (ref "U2") (pin "26") (pinfunction "PB0_26") (pintype "bidirectional"))
    )
    (net (code "54") (name "unconnected-(U2-PB1-Pad27)") (class "Default")
      (node (ref "U2") (pin "27") (pinfunction "PB1_27") (pintype "bidirectional"))
    )
    (net (code "55") (name "unconnected-(U2-PB3-Pad55)") (class "Default")
      (node (ref "U2") (pin "55") (pinfunction "PB3_55") (pintype "bidirectional"))
    )
    (net (code "56") (name "unconnected-(U2-PB4-Pad56)") (class "Default")
      (node (ref "U2") (pin "56") (pinfunction "PB4_56") (pintype "bidirectional"))
    )
    (net (code "57") (name "unconnected-(U2-PB5-Pad57)") (class "Default")
      (node (ref "U2") (pin "57") (pinfunction "PB5_57") (pintype "bidirectional"))
    )
    (net (code "58") (name "unconnected-(U2-PB6-Pad58)") (class "Default")
      (node (ref "U2") (pin "58") (pinfunction "PB6_58") (pintype "bidirectional"))
    )
    (net (code "59") (name "unconnected-(U2-PB10-Pad29)") (class "Default")
      (node (ref "U2") (pin "29") (pinfunction "PB10_29") (pintype "bidirectional"))
    )
    (net (code "60") (name "unconnected-(U2-PB12-Pad33)") (class "Default")
      (node (ref "U2") (pin "33") (pinfunction "PB12_33") (pintype "bidirectional"))
    )
    (net (code "61") (name "unconnected-(U2-PB13-Pad34)") (class "Default")
      (node (ref "U2") (pin "34") (pinfunction "PB13_34") (pintype "bidirectional"))
    )
    (net (code "62") (name "unconnected-(U2-PB14-Pad35)") (class "Default")
      (node (ref "U2") (pin "35") (pinfunction "PB14_35") (pintype "bidirectional"))
    )
    (net (code "63") (name "unconnected-(U2-PB15-Pad36)") (class "Default")
      (node (ref "U2") (pin "36") (pinfunction "PB15_36") (pintype "bidirectional"))
    )
    (net (code "64") (name "unconnected-(U2-PC0-Pad8)") (class "Default")
      (node (ref "U2") (pin "8") (pinfunction "PC0_8") (pintype "bidirectional"))
    )
    (net (code "65") (name "unconnected-(U2-PC1-Pad9)") (class "Default")
      (node (ref "U2") (pin "9") (pinfunction "PC1_9") (pintype "bidirectional"))
    )
    (net (code "66") (name "unconnected-(U2-PC2-Pad10)") (class "Default")
      (node (ref "U2") (pin "10") (pinfunction "PC2_10") (pintype "bidirectional"))
    )
    (net (code "67") (name "unconnected-(U2-PC3-Pad11)") (class "Default")
      (node (ref "U2") (pin "11") (pinfunction "PC3_11") (pintype "bidirectional"))
    )
    (net (code "68") (name "unconnected-(U2-PC4-Pad24)") (class "Default")
      (node (ref "U2") (pin "24") (pinfunction "PC4_24") (pintype "bidirectional"))
    )
    (net (code "69") (name "unconnected-(U2-PC5-Pad25)") (class "Default")
      (node (ref "U2") (pin "25") (pinfunction "PC5_25") (pintype "bidirectional"))
    )
    (net (code "70") (name "unconnected-(U2-PC6-Pad37)") (class "Default")
      (node (ref "U2") (pin "37") (pinfunction "PC6_37") (pintype "bidirectional"))
    )
    (net (code "71") (name "unconnected-(U2-PC7-Pad38)") (class "Default")
      (node (ref "U2") (pin "38") (pinfunction "PC7_38") (pintype "bidirectional"))
    )
    (net (code "72") (name "unconnected-(U2-PC8-Pad39)") (class "Default")
      (node (ref "U2") (pin "39") (pinfunction "PC8_39") (pintype "bidirectional"))
    )
    (net (code "73") (name "unconnected-(U2-PC9-Pad40)") (class "Default")
      (node (ref "U2") (pin "40") (pinfunction "PC9_40") (pintype "bidirectional"))
    )
    (net (code "74") (name "unconnected-(U2-PC10-Pad51)") (class "Default")
      (node (ref "U2") (pin "51") (pinfunction "PC10_51") (pintype "bidirectional"))
    )
    (net (code "75") (name "unconnected-(U2-PC11-Pad52)") (class "Default")
      (node (ref "U2") (pin "52") (pinfunction "PC11_52") (pintype "bidirectional"))
    )
    (net (code "76") (name "unconnected-(U2-PC13-Pad2)") (class "Default")
      (node (ref "U2") (pin "2") (pinfunction "PC13_2") (pintype "bidirectional"))
    )
    (net (code "77") (name "unconnected-(U2-PC14-OSC32_IN-Pad3)") (class "Default")
      (node (ref "U2") (pin "3") (pinfunction "PC14-OSC32_IN_3") (pintype "bidirectional"))
    )
    (net (code "78") (name "unconnected-(U2-PC15-OSC32_OUT-Pad4)") (class "Default")
      (node (ref "U2") (pin "4") (pinfunction "PC15-OSC32_OUT_4") (pintype "bidirectional"))
    )
    (net (code "79") (name "unconnected-(U2-PD2-Pad54)") (class "Default")
      (node (ref "U2") (pin "54") (pinfunction "PD2_54") (pintype "bidirectional"))
    )
    (net (code "80") (name "unconnected-(U2-VCAP_1-Pad30)") (class "Default")
      (node (ref "U2") (pin "30") (pinfunction "VCAP_1_30") (pintype "power_in"))
    )
    (net (code "81") (name "unconnected-(U3-3A-Pad9)") (class "Default")
      (node (ref "U3") (pin "9") (pinfunction "3A_9") (pintype "input"))
    )
    (net (code "82") (name "unconnected-(U4-Cd-Pad9)") (class "Default")
      (node (ref "U4") (pin "9") (pinfunction "Cd_9") (pintype "passive"))
    )
    (net (code "83") (name "unconnected-(U4-DAT1-Pad8)") (class "Default")
      (node (ref "U4") (pin "8") (pinfunction "DAT1_8") (pintype "passive"))
    )
    (net (code "84") (name "unconnected-(U4-DAT2-Pad1)") (class "Default")
      (node (ref "U4") (pin "1") (pinfunction "DAT2_1") (pintype "passive"))
    )
    (net (code "85") (name "unconnected-(U5-AD0-Pad9)") (class "Default")
      (node (ref "U5") (pin "9") (pinfunction "AD0_9") (pintype "input"))
    )
    (net (code "86") (name "unconnected-(U5-AUX_CL-Pad7)") (class "Default")
      (node (ref "U5") (pin "7") (pinfunction "AUX_CL_7") (pintype "input"))
    )
    (net (code "87") (name "unconnected-(U5-AUX_DA-Pad6)") (class "Default")
      (node (ref "U5") (pin "6") (pinfunction "AUX_DA_6") (pintype "bidirectional"))
    )
    (net (code "88") (name "unconnected-(U5-INT-Pad12)") (class "Default")
      (node (ref "U5") (pin "12") (pinfunction "INT_12") (pintype "output"))
    )
    (net (code "89") (name "unconnected-(U6-DRDY-Pad15)") (class "Default")
      (node (ref "U6") (pin "15") (pinfunction "DRDY_15") (pintype "passive"))
    )
    (net (code "90") (name "unconnected-(U6-NC-Pad3)") (class "Default")
      (node (ref "U6") (pin "3") (pinfunction "NC_3") (pintype "passive"))
    )
    (net (code "91") (name "unconnected-(U6-NC-Pad5)") (class "Default")
      (node (ref "U6") (pin "5") (pinfunction "NC_5") (pintype "passive"))
    )
    (net (code "92") (name "unconnected-(U6-NC-Pad6)") (class "Default")
      (node (ref "U6") (pin "6") (pinfunction "NC_6") (pintype "passive"))
    )
    (net (code "93") (name "unconnected-(U6-NC-Pad7)") (class "Default")
      (node (ref "U6") (pin "7") (pinfunction "NC_7") (pintype "passive"))
    )
    (net (code "94") (name "unconnected-(U6-NC-Pad14)") (class "Default")
      (node (ref "U6") (pin "14") (pinfunction "NC_14") (pintype "passive"))
    )
  )
)
